# IRComputer.net
KiCad netlist of a schematic drawn in EAGLE
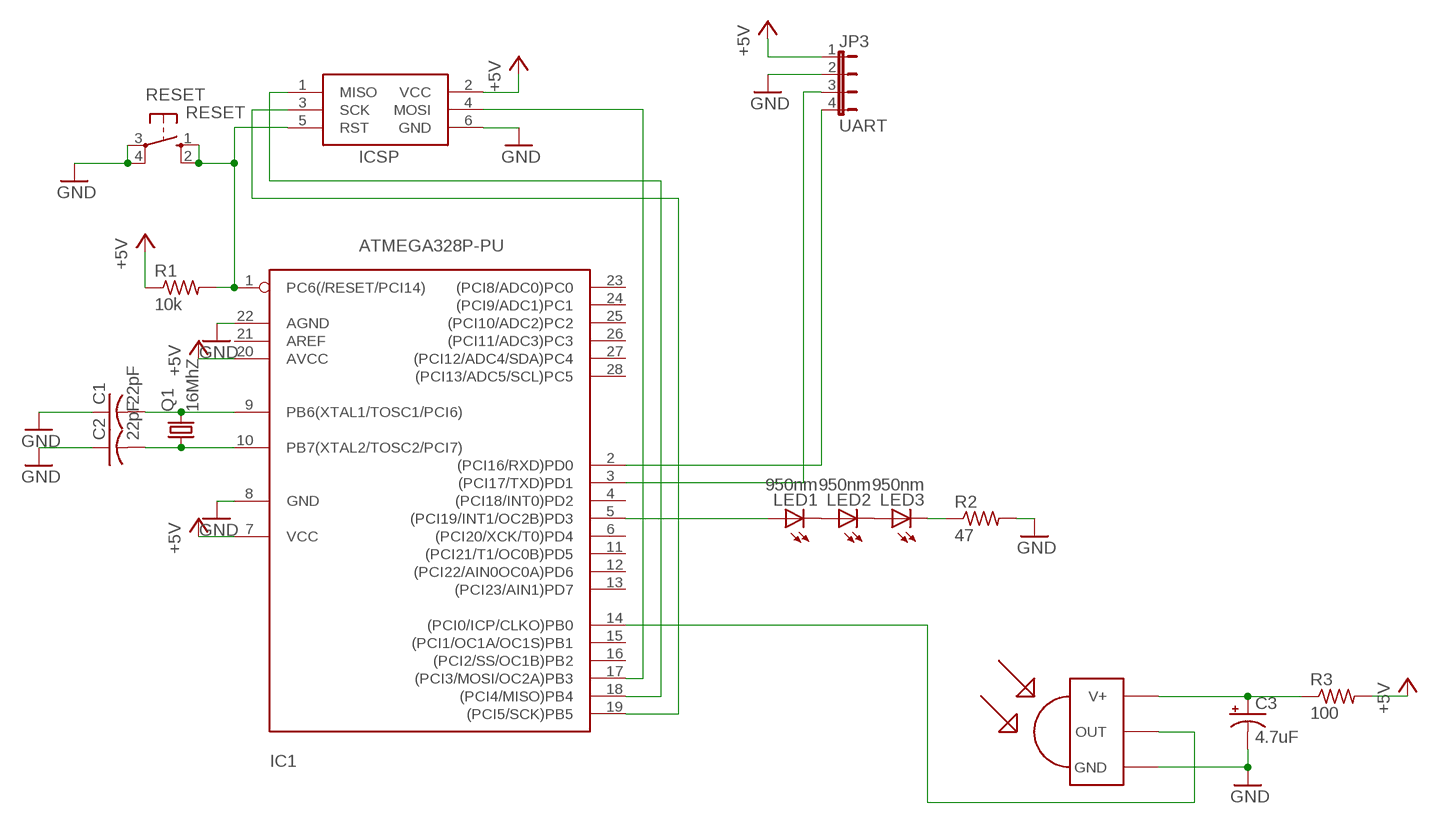
[diagram p0: schematic, sheet 1]

(export (version "E")
  (design (tool "Eeschema 10.0.6"))
  (components
    (comp (ref "C1")
      (value "22pF")
      (footprint "eagle-import:C025-024X044")
      (libsource (lib "eagle-import") (part "C-US025-024X044"))
    )
    (comp (ref "C2")
      (value "22pF")
      (footprint "eagle-import:C025-024X044")
      (libsource (lib "eagle-import") (part "C-US025-024X044"))
    )
    (comp (ref "C3")
      (value "4.7uF")
      (footprint "eagle-import:E1,8-4")
      (libsource (lib "eagle-import") (part "CPOL-USE1.8-4"))
    )
    (comp (ref "IC1")
      (value "ATMEGA328P-PU")
      (footprint "eagle-import:DIL28-3")
      (libsource (lib "eagle-import") (part "ATMEGA168P-20"))
    )
    (comp (ref "ICSP")
      (value "AVRISP-6")
      (footprint "eagle-import:AVRISP")
      (libsource (lib "eagle-import") (part "AVRISP-6"))
    )
    (comp (ref "JP3")
      (value "UART")
      (footprint "eagle-import:JP4")
      (libsource (lib "eagle-import") (part "JP4E"))
    )
    (comp (ref "LED1")
      (value "950nm")
      (footprint "eagle-import:LED5MM")
      (libsource (lib "eagle-import") (part "LED5MM"))
    )
    (comp (ref "LED2")
      (value "950nm")
      (footprint "eagle-import:LED5MM")
      (libsource (lib "eagle-import") (part "LED5MM"))
    )
    (comp (ref "LED3")
      (value "950nm")
      (footprint "eagle-import:LED5MM")
      (libsource (lib "eagle-import") (part "LED5MM"))
    )
    (comp (ref "Q1")
      (value "16MhZ")
      (footprint "eagle-import:HC49_S")
      (libsource (lib "eagle-import") (part "CRYSTALHC49S"))
    )
    (comp (ref "R1")
      (value "10k")
      (footprint "eagle-import:0204_7")
      (libsource (lib "eagle-import") (part "R-US_0204/7"))
    )
    (comp (ref "R2")
      (value "47")
      (footprint "eagle-import:0204_7")
      (libsource (lib "eagle-import") (part "R-US_0204/7"))
    )
    (comp (ref "R3")
      (value "100")
      (footprint "eagle-import:0204_7")
      (libsource (lib "eagle-import") (part "R-US_0204/7"))
    )
    (comp (ref "RESET")
      (value "RESET")
      (footprint "eagle-import:B3F-10XX")
      (fields (field (name "MPN") "B3F-1000"))
      (libsource (lib "eagle-import") (part "10-XX"))
    )
    (comp (ref "U$1")
      (value "TSOP1838")
      (footprint "eagle-import:TSOP18XX")
      (libsource (lib "eagle-import") (part "TSOP1838"))
    )
  )
  (nets
    (net (code "1") (name "+5V") (class "Default")
      (node (ref "IC1") (pin "20") (pinfunction "AVCC_20") (pintype "bidirectional"))
      (node (ref "IC1") (pin "7") (pinfunction "VCC_7") (pintype "bidirectional"))
      (node (ref "ICSP") (pin "2") (pinfunction "VCC_2") (pintype "power_in"))
      (node (ref "JP3") (pin "1") (pinfunction "1_1") (pintype "passive"))
      (node (ref "R1") (pin "1") (pinfunction "1_1") (pintype "passive"))
      (node (ref "R3") (pin "2") (pinfunction "2_2") (pintype "passive"))
    )
    (net (code "2") (name "GND") (class "Default")
      (node (ref "C1") (pin "1") (pinfunction "1_1") (pintype "passive"))
      (node (ref "C2") (pin "1") (pinfunction "1_1") (pintype "passive"))
      (node (ref "C3") (pin "-") (pinfunction "-_-") (pintype "passive"))
      (node (ref "IC1") (pin "22") (pinfunction "AGND_22") (pintype "bidirectional"))
      (node (ref "IC1") (pin "8") (pinfunction "GND_8") (pintype "bidirectional"))
      (node (ref "ICSP") (pin "6") (pinfunction "GND_6") (pintype "power_in"))
      (node (ref "JP3") (pin "2") (pinfunction "2_2") (pintype "passive"))
      (node (ref "R2") (pin "2") (pinfunction "2_2") (pintype "passive"))
      (node (ref "RESET") (pin "3") (pinfunction "P_3") (pintype "passive"))
      (node (ref "RESET") (pin "4") (pinfunction "P1_4") (pintype "passive"))
      (node (ref "U$1") (pin "GND") (pinfunction "GND_GND") (pintype "bidirectional"))
    )
    (net (code "3") (name "Net-(IC1-(PCI0{slash}ICP{slash}CLKO)PB0)") (class "Default")
      (node (ref "IC1") (pin "14") (pinfunction "(PCI0/ICP/CLKO)PB0_14") (pintype "bidirectional"))
      (node (ref "U$1") (pin "OUT") (pinfunction "OUT_OUT") (pintype "bidirectional"))
    )
    (net (code "4") (name "Net-(IC1-(PCI3{slash}MOSI{slash}OC2A)PB3)") (class "Default")
      (node (ref "IC1") (pin "17") (pinfunction "(PCI3/MOSI/OC2A)PB3_17") (pintype "bidirectional"))
      (node (ref "ICSP") (pin "4") (pinfunction "MOSI_4") (pintype "output"))
    )
    (net (code "5") (name "Net-(IC1-(PCI4{slash}MISO)PB4)") (class "Default")
      (node (ref "IC1") (pin "18") (pinfunction "(PCI4/MISO)PB4_18") (pintype "bidirectional"))
      (node (ref "ICSP") (pin "1") (pinfunction "MISO_1") (pintype "input"))
    )
    (net (code "6") (name "Net-(IC1-(PCI5{slash}SCK)PB5)") (class "Default")
      (node (ref "IC1") (pin "19") (pinfunction "(PCI5/SCK)PB5_19") (pintype "bidirectional"))
      (node (ref "ICSP") (pin "3") (pinfunction "SCK_3") (pintype "output"))
    )
    (net (code "7") (name "Net-(IC1-(PCI16{slash}RXD)PD0)") (class "Default")
      (node (ref "IC1") (pin "2") (pinfunction "(PCI16/RXD)PD0_2") (pintype "bidirectional"))
      (node (ref "JP3") (pin "4") (pinfunction "4_4") (pintype "passive"))
    )
    (net (code "8") (name "Net-(IC1-(PCI17{slash}TXD)PD1)") (class "Default")
      (node (ref "IC1") (pin "3") (pinfunction "(PCI17/TXD)PD1_3") (pintype "bidirectional"))
      (node (ref "JP3") (pin "3") (pinfunction "3_3") (pintype "passive"))
    )
    (net (code "9") (name "Net-(IC1-(PCI19{slash}INT1{slash}OC2B)PD3)") (class "Default")
      (node (ref "IC1") (pin "5") (pinfunction "(PCI19/INT1/OC2B)PD3_5") (pintype "bidirectional"))
      (node (ref "LED1") (pin "A") (pinfunction "A_A") (pintype "passive"))
    )
    (net (code "10") (name "Net-(IC1-PB6(XTAL1{slash}TOSC1{slash}PCI6))") (class "Default")
      (node (ref "C1") (pin "2") (pinfunction "2_2") (pintype "passive"))
      (node (ref "IC1") (pin "9") (pinfunction "PB6(XTAL1/TOSC1/PCI6)_9") (pintype "bidirectional"))
      (node (ref "Q1") (pin "2") (pinfunction "2_2") (pintype "passive"))
    )
    (net (code "11") (name "Net-(IC1-PB7(XTAL2{slash}TOSC2{slash}PCI7))") (class "Default")
      (node (ref "C2") (pin "2") (pinfunction "2_2") (pintype "passive"))
      (node (ref "IC1") (pin "10") (pinfunction "PB7(XTAL2/TOSC2/PCI7)_10") (pintype "bidirectional"))
      (node (ref "Q1") (pin "1") (pinfunction "1_1") (pintype "passive"))
    )
    (net (code "12") (name "Net-(IC1-PC6({slash}RESET{slash}PCI14))") (class "Default")
      (node (ref "IC1") (pin "1") (pinfunction "PC6(/RESET/PCI14)_1") (pintype "bidirectional"))
      (node (ref "ICSP") (pin "5") (pinfunction "RST_5") (pintype "output"))
      (node (ref "R1") (pin "2") (pinfunction "2_2") (pintype "passive"))
      (node (ref "RESET") (pin "1") (pinfunction "S_1") (pintype "passive"))
      (node (ref "RESET") (pin "2") (pinfunction "S1_2") (pintype "passive"))
    )
    (net (code "13") (name "Net-(LED1-C)") (class "Default")
      (node (ref "LED1") (pin "K") (pinfunction "C_K") (pintype "passive"))
      (node (ref "LED2") (pin "A") (pinfunction "A_A") (pintype "passive"))
    )
    (net (code "14") (name "Net-(LED2-C)") (class "Default")
      (node (ref "LED2") (pin "K") (pinfunction "C_K") (pintype "passive"))
      (node (ref "LED3") (pin "A") (pinfunction "A_A") (pintype "passive"))
    )
    (net (code "15") (name "Net-(LED3-C)") (class "Default")
      (node (ref "LED3") (pin "K") (pinfunction "C_K") (pintype "passive"))
      (node (ref "R2") (pin "1") (pinfunction "1_1") (pintype "passive"))
    )
    (net (code "16") (name "Net-(U$1-V+)") (class "Default")
      (node (ref "C3") (pin "+") (pinfunction "+_+") (pintype "passive"))
      (node (ref "R3") (pin "1") (pinfunction "1_1") (pintype "passive"))
      (node (ref "U$1") (pin "VCC") (pinfunction "V+_VCC") (pintype "bidirectional"))
    )
    (net (code "17") (name "unconnected-(IC1-(PCI1{slash}OC1A{slash}OC1S)PB1-Pad15)") (class "Default")
      (node (ref "IC1") (pin "15") (pinfunction "(PCI1/OC1A/OC1S)PB1_15") (pintype "bidirectional"))
    )
    (net (code "18") (name "unconnected-(IC1-(PCI2{slash}SS{slash}OC1B)PB2-Pad16)") (class "Default")
      (node (ref "IC1") (pin "16") (pinfunction "(PCI2/SS/OC1B)PB2_16") (pintype "bidirectional"))
    )
    (net (code "19") (name "unconnected-(IC1-(PCI8{slash}ADC0)PC0-Pad23)") (class "Default")
      (node (ref "IC1") (pin "23") (pinfunction "(PCI8/ADC0)PC0_23") (pintype "bidirectional"))
    )
    (net (code "20") (name "unconnected-(IC1-(PCI9{slash}ADC1)PC1-Pad24)") (class "Default")
      (node (ref "IC1") (pin "24") (pinfunction "(PCI9/ADC1)PC1_24") (pintype "bidirectional"))
    )
    (net (code "21") (name "unconnected-(IC1-(PCI10{slash}ADC2)PC2-Pad25)") (class "Default")
      (node (ref "IC1") (pin "25") (pinfunction "(PCI10/ADC2)PC2_25") (pintype "bidirectional"))
    )
    (net (code "22") (name "unconnected-(IC1-(PCI11{slash}ADC3)PC3-Pad26)") (class "Default")
      (node (ref "IC1") (pin "26") (pinfunction "(PCI11/ADC3)PC3_26") (pintype "bidirectional"))
    )
    (net (code "23") (name "unconnected-(IC1-(PCI12{slash}ADC4{slash}SDA)PC4-Pad27)") (class "Default")
      (node (ref "IC1") (pin "27") (pinfunction "(PCI12/ADC4/SDA)PC4_27") (pintype "bidirectional"))
    )
    (net (code "24") (name "unconnected-(IC1-(PCI13{slash}ADC5{slash}SCL)PC5-Pad28)") (class "Default")
      (node (ref "IC1") (pin "28") (pinfunction "(PCI13/ADC5/SCL)PC5_28") (pintype "bidirectional"))
    )
    (net (code "25") (name "unconnected-(IC1-(PCI18{slash}INT0)PD2-Pad4)") (class "Default")
      (node (ref "IC1") (pin "4") (pinfunction "(PCI18/INT0)PD2_4") (pintype "bidirectional"))
    )
    (net (code "26") (name "unconnected-(IC1-(PCI20{slash}XCK{slash}T0)PD4-Pad6)") (class "Default")
      (node (ref "IC1") (pin "6") (pinfunction "(PCI20/XCK/T0)PD4_6") (pintype "bidirectional"))
    )
    (net (code "27") (name "unconnected-(IC1-(PCI21{slash}T1{slash}OC0B)PD5-Pad11)") (class "Default")
      (node (ref "IC1") (pin "11") (pinfunction "(PCI21/T1/OC0B)PD5_11") (pintype "bidirectional"))
    )
    (net (code "28") (name "unconnected-(IC1-(PCI22{slash}AIN0OC0A)PD6-Pad12)") (class "Default")
      (node (ref "IC1") (pin "12") (pinfunction "(PCI22/AIN0OC0A)PD6_12") (pintype "bidirectional"))
    )
    (net (code "29") (name "unconnected-(IC1-(PCI23{slash}AIN1)PD7-Pad13)") (class "Default")
      (node (ref "IC1") (pin "13") (pinfunction "(PCI23/AIN1)PD7_13") (pintype "bidirectional"))
    )
    (net (code "30") (name "unconnected-(IC1-AREF-Pad21)") (class "Default")
      (node (ref "IC1") (pin "21") (pinfunction "AREF_21") (pintype "bidirectional"))
    )
  )
)
